# Ultrasound.net
KiCad netlist of a schematic drawn in Altium Designer
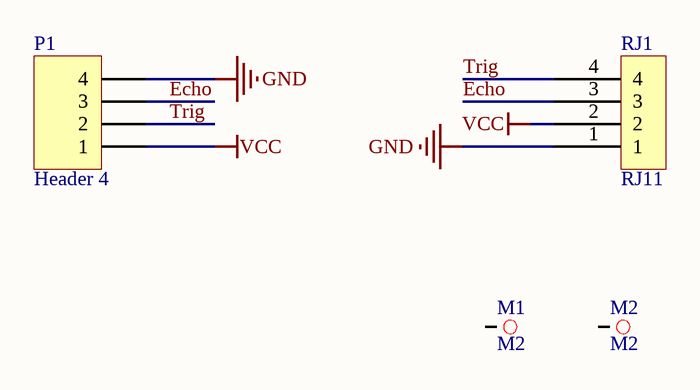
[diagram p0: Ultrasound.SchDoc]

(export (version "E")
  (design (tool "Eeschema 10.0.6"))
  (components
    (comp (ref "M1") (value "M2") (footprint "M2") (libsource (lib "QQW-1.SCHLIB") (part "M3")))
    (comp (ref "M2") (value "M2") (footprint "M2") (libsource (lib "QQW-1.SCHLIB") (part "M3")))
    (comp (ref "P1")
      (value "Header 4")
      (footprint "HDR1X4")
      (description "Header, 4-Pin")
      (fields (field (name "PUBLISHER") "Altium Limited"))
      (libsource (lib "Miscellaneous Connectors") (part "Header 4"))
    )
    (comp (ref "RJ1") (value "RJ11") (footprint "RJ11") (libsource (lib "少儿智能车") (part "RJ11")))
  )
  (nets
    (net (code "1") (name "/Echo") (class "Default")
      (node (ref "P1") (pin "3") (pinfunction "3_3") (pintype "passive"))
      (node (ref "RJ1") (pin "3") (pinfunction "3_3") (pintype "passive"))
    )
    (net (code "2") (name "/Trig") (class "Default")
      (node (ref "P1") (pin "2") (pinfunction "2_2") (pintype "passive"))
      (node (ref "RJ1") (pin "4") (pinfunction "4_4") (pintype "passive"))
    )
    (net (code "3") (name "GND") (class "Default")
      (node (ref "P1") (pin "4") (pinfunction "4_4") (pintype "passive"))
      (node (ref "RJ1") (pin "1") (pinfunction "1_1") (pintype "passive"))
    )
    (net (code "4") (name "VCC") (class "Default")
      (node (ref "P1") (pin "1") (pinfunction "1_1") (pintype "passive"))
      (node (ref "RJ1") (pin "2") (pinfunction "2_2") (pintype "passive"))
    )
    (net (code "5") (name "unconnected-(M1-Pad0)") (class "Default")
      (node (ref "M1") (pin "0") (pinfunction "0_0") (pintype "passive"))
    )
    (net (code "6") (name "unconnected-(M2-Pad0)") (class "Default")
      (node (ref "M2") (pin "0") (pinfunction "0_0") (pintype "passive"))
    )
  )
)
